# pca10040_sheet7_power_supply.net
KiCad netlist of a schematic drawn in Altium Designer
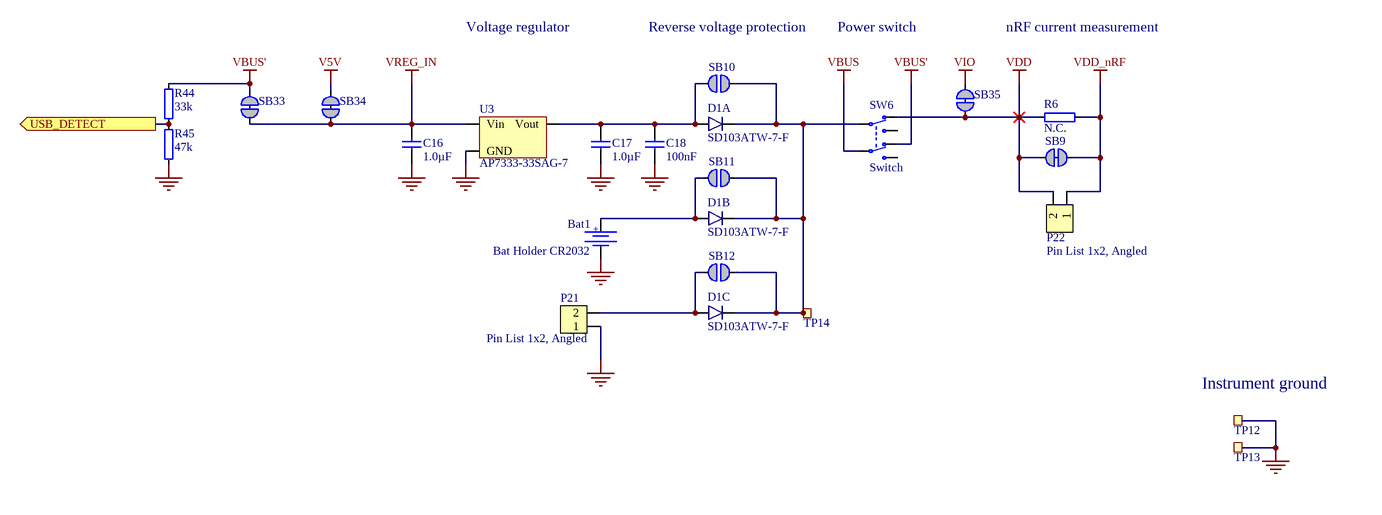
[diagram p0: pca10040_sheet7_power_supply.SchDoc]

(export (version "E")
  (design (tool "Eeschema 10.0.6"))
  (components
    (comp (ref "Bat1")
      (value "Bat Holder CR2032")
      (footprint "CR2032_HOLDER_SMD")
      (description "Bat Holder CR2032 SMD")
      (fields
        (field (name "MANUFACTURER") "Comfortable")
        (field (name "MANUFACTURER PART NUMBER") "BC-2001")
        (field (name "PUBLISHER") "Nordic Semiconductor")
      )
      (libsource (lib "Nordic Passive DB") (part "Battery"))
    )
    (comp (ref "C16")
      (value "1.0µF")
      (footprint "CAPC1608X06L")
      (description "Capacitor, X7R, ±10%")
      (fields (field (name "PART NUMBER") "C0603-1µ0") (field (name "PUBLISHER") "Nordic Semiconductor"))
      (libsource (lib "Nordic Passive DB") (part "CAP"))
    )
    (comp (ref "C17")
      (value "1.0µF")
      (footprint "CAPC1608X06L")
      (description "Capacitor, X7R, ±10%")
      (fields (field (name "PART NUMBER") "C0603-1µ0") (field (name "PUBLISHER") "Nordic Semiconductor"))
      (libsource (lib "Nordic Passive DB") (part "CAP"))
    )
    (comp (ref "C18")
      (value "100nF")
      (footprint "CAPC1005X04L")
      (description "Capacitor, X7R, ±10%")
      (fields (field (name "PART NUMBER") "C0402-100n") (field (name "PUBLISHER") "Nordic Semiconductor"))
      (libsource (lib "Nordic Passive DB") (part "CAP"))
    )
    (comp (ref "D1")
      (value "SD103ATW-7-F")
      (footprint "SOT-363")
      (description "Surface Mount Schottky Barrier Diode Array")
      (fields
        (field (name "MANUFACTURER") "Diodes Incorporated")
        (field (name "2ND SOURCE PART NUMBER") "177-3507")
        (field (name "PUBLISHER") "Nordic Semiconductor")
      )
      (libsource (lib "Nordic Discrete DB") (part "D{colon}DIODE_3_IND"))
    )
    (comp (ref "P21")
      (value "Pin List 1x2, Angled")
      (footprint "LIST_ANG_1x2-SMD-2.54MM")
      (description "Pin List 1x2, 2.54mm (100mil), Right Angled, SMD")
      (fields
        (field (name "PART NUMBER") "Pin List Ang 1x2 SMD, 2.54mm")
        (field (name "MANUFACTURER") "W-CON")
        (field (name "PUBLISHER") "Nordic Semiconductor")
      )
      (libsource (lib "") (part "CONN-2_1"))
    )
    (comp (ref "P22")
      (value "Pin List 1x2, Angled")
      (footprint "LIST_ANG_1x2-SMD-2.54MM")
      (description "Pin List 1x2, 2.54mm (100mil), Right Angled, SMD")
      (fields
        (field (name "PART NUMBER") "Pin List Ang 1x2 SMD, 2.54mm")
        (field (name "MANUFACTURER") "W-CON")
        (field (name "PUBLISHER") "Nordic Semiconductor")
      )
      (libsource (lib "Nordic Passive DB") (part "CONN-2"))
    )
    (comp (ref "R6")
      (value "N.C.")
      (footprint "RESC1005X04L")
      (description "Not mounted")
      (fields (field (name "PART NUMBER") "R0402-N.C.") (field (name "PUBLISHER") "Nordic Semiconductor"))
      (libsource (lib "Nordic Passive DB") (part "RES_1"))
    )
    (comp (ref "R44")
      (value "33k")
      (footprint "RESC1005X04L")
      (description "Resistor, ±1%, 0.063W")
      (fields (field (name "PART NUMBER") "R0402-33k") (field (name "PUBLISHER") "Nordic Semiconductor"))
      (libsource (lib "Nordic Passive DB") (part "RES_1"))
    )
    (comp (ref "R45")
      (value "47k")
      (footprint "RESC1005X04L")
      (description "Resistor, ±1%, 0.063W")
      (fields (field (name "PART NUMBER") "R0402-47k") (field (name "PUBLISHER") "Nordic Semiconductor"))
      (libsource (lib "Nordic Passive DB") (part "RES_1"))
    )
    (comp (ref "SB9")
      (value "Solderbridge")
      (footprint "Solderbridge_Shorted")
      (description "Shorted Solderbridge")
      (fields
        (field (name "PART NUMBER") "Solderbridge Shorted")
        (field (name "PUBLISHER") "Nordic Semiconductor")
      )
      (libsource (lib "Nordic Passive DB") (part "SOLDERBRIDGE_SHORTED"))
    )
    (comp (ref "SB10")
      (value "Solderbridge")
      (footprint "Solderbridge")
      (fields (field (name "PUBLISHER") "Nordic Semiconductor"))
      (libsource (lib "Nordic Passive DB") (part "SOLDERBRIDGE"))
    )
    (comp (ref "SB11")
      (value "Solderbridge")
      (footprint "Solderbridge")
      (fields (field (name "PUBLISHER") "Nordic Semiconductor"))
      (libsource (lib "Nordic Passive DB") (part "SOLDERBRIDGE"))
    )
    (comp (ref "SB12")
      (value "Solderbridge")
      (footprint "Solderbridge")
      (fields (field (name "PUBLISHER") "Nordic Semiconductor"))
      (libsource (lib "Nordic Passive DB") (part "SOLDERBRIDGE"))
    )
    (comp (ref "SB33")
      (value "Solderbridge")
      (footprint "Solderbridge_Shorted_Power")
      (description "Shorted Solderbridge Power")
      (fields
        (field (name "PART NUMBER") "Solderbridge Shorted Power")
        (field (name "PUBLISHER") "Nordic Semiconductor")
      )
      (libsource (lib "Nordic Passive DB") (part "SOLDERBRIDGE_SHORTED"))
    )
    (comp (ref "SB34")
      (value "Solderbridge")
      (footprint "Solderbridge_Shorted_Power")
      (description "Shorted Solderbridge Power")
      (fields
        (field (name "PART NUMBER") "Solderbridge Shorted Power")
        (field (name "PUBLISHER") "Nordic Semiconductor")
      )
      (libsource (lib "Nordic Passive DB") (part "SOLDERBRIDGE_SHORTED"))
    )
    (comp (ref "SB35")
      (value "Solderbridge")
      (footprint "Solderbridge_Shorted_Power")
      (description "Shorted Solderbridge Power")
      (fields
        (field (name "PART NUMBER") "Solderbridge Shorted Power")
        (field (name "PUBLISHER") "Nordic Semiconductor")
      )
      (libsource (lib "Nordic Passive DB") (part "SOLDERBRIDGE_SHORTED"))
    )
    (comp (ref "SW6")
      (value "Switch")
      (footprint "Switch-Slide-DPDT-8.5x3.6mm")
      (description "SMD slide Switch (ON-ON)")
      (fields
        (field (name "PART NUMBER") "Switch-Slide-DPDT-8.5x3.6mm")
        (field (name "MANUFACTURER") "Dailywell")
        (field (name "PUBLISHER") "Nordic Semiconductor")
      )
      (libsource (lib "Nordic Discrete DB") (part "SW-DPDT"))
    )
    (comp (ref "TP12")
      (value "TP")
      (footprint "TESTPAD-TH")
      (description "Testpoint, through hole")
      (fields (field (name "PART NUMBER") "Testpoint TH") (field (name "PUBLISHER") "Nordic Semiconductor"))
      (libsource (lib "Nordic Passive DB") (part "TESTPAD"))
    )
    (comp (ref "TP13")
      (value "TP")
      (footprint "TESTPAD-TH")
      (description "Testpoint, through hole")
      (fields (field (name "PART NUMBER") "Testpoint TH") (field (name "PUBLISHER") "Nordic Semiconductor"))
      (libsource (lib "Nordic Passive DB") (part "TESTPAD"))
    )
    (comp (ref "TP14")
      (value "Ø1.0mm,SMD")
      (footprint "TP_SMD_Ø1.0mm")
      (description "1.0mm circular SMD testpad")
      (fields
        (field (name "PART NUMBER") "TP_SMD_Ø1.0MM")
        (field (name "MANUFACTURER") "Nordic Semiconductor")
        (field (name "PUBLISHER") "Nordic Semiconductor")
      )
      (libsource (lib "") (part "TESTPAD_1"))
    )
    (comp (ref "U3")
      (value "AP7333-33SAG-7")
      (footprint "SOT-23A")
      (description "300mA, Low Quiescent Current, Fast Transient Low Dropout Linear Regulator")
      (fields
        (field (name "MANUFACTURER") "Diodes Incorporated")
        (field (name "PUBLISHER") "Nordic Semiconductor")
      )
      (libsource (lib "Nordic Active DB") (part "AP7333-XXSAG"))
    )
  )
  (nets
    (net (code "1") (name "/USB_DETECT") (class "Default")
      (node (ref "R44") (pin "1") (pinfunction "1_1") (pintype "passive"))
      (node (ref "R45") (pin "2") (pinfunction "2_2") (pintype "passive"))
    )
    (net (code "2") (name "GND") (class "Default")
      (node (ref "Bat1") (pin "2") (pintype "passive"))
      (node (ref "C16") (pin "1") (pinfunction "1_1") (pintype "passive"))
      (node (ref "C17") (pin "1") (pinfunction "1_1") (pintype "passive"))
      (node (ref "C18") (pin "1") (pinfunction "1_1") (pintype "passive"))
      (node (ref "P21") (pin "1") (pinfunction "1_1") (pintype "passive"))
      (node (ref "R45") (pin "1") (pinfunction "1_1") (pintype "passive"))
      (node (ref "TP12") (pin "1") (pinfunction "1_1") (pintype "passive"))
      (node (ref "TP13") (pin "1") (pinfunction "1_1") (pintype "passive"))
      (node (ref "U3") (pin "3") (pinfunction "GND_3") (pintype "passive"))
    )
    (net (code "3") (name "Net-(D1A-A1)") (class "Default")
      (node (ref "C17") (pin "2") (pinfunction "2_2") (pintype "passive"))
      (node (ref "C18") (pin "2") (pinfunction "2_2") (pintype "passive"))
      (node (ref "D1") (pin "6") (pinfunction "A1_6") (pintype "passive"))
      (node (ref "SB10") (pin "2") (pinfunction "1_2") (pintype "passive"))
      (node (ref "U3") (pin "2") (pinfunction "Vout_2") (pintype "passive"))
    )
    (net (code "4") (name "Net-(D1A-C1)") (class "Default")
      (node (ref "D1") (pin "1") (pinfunction "C1_1") (pintype "passive"))
      (node (ref "D1") (pin "2") (pinfunction "C2_2") (pintype "passive"))
      (node (ref "D1") (pin "3") (pinfunction "C3_3") (pintype "passive"))
      (node (ref "SB10") (pin "1") (pinfunction "0_1") (pintype "passive"))
      (node (ref "SB11") (pin "1") (pinfunction "0_1") (pintype "passive"))
      (node (ref "SB12") (pin "1") (pinfunction "0_1") (pintype "passive"))
      (node (ref "SW6") (pin "2") (pinfunction "COM-1_2") (pintype "passive"))
      (node (ref "TP14") (pin "1") (pinfunction "1_1") (pintype "passive"))
    )
    (net (code "5") (name "Net-(D1B-A2)") (class "Default")
      (node (ref "Bat1") (pin "1") (pintype "passive"))
      (node (ref "D1") (pin "5") (pinfunction "A2_5") (pintype "passive"))
      (node (ref "SB11") (pin "2") (pinfunction "1_2") (pintype "passive"))
    )
    (net (code "6") (name "Net-(D1C-A3)") (class "Default")
      (node (ref "D1") (pin "4") (pinfunction "A3_4") (pintype "passive"))
      (node (ref "P21") (pin "2") (pinfunction "2_2") (pintype "passive"))
      (node (ref "SB12") (pin "2") (pinfunction "1_2") (pintype "passive"))
    )
    (net (code "7") (name "V5V") (class "Default")
      (node (ref "SB34") (pin "1") (pinfunction "0_1") (pintype "passive"))
    )
    (net (code "8") (name "VBUS") (class "Default")
      (node (ref "SW6") (pin "5") (pinfunction "COM-2_5") (pintype "passive"))
    )
    (net (code "9") (name "VBUS'") (class "Default")
      (node (ref "R44") (pin "2") (pinfunction "2_2") (pintype "passive"))
      (node (ref "SB33") (pin "1") (pinfunction "0_1") (pintype "passive"))
      (node (ref "SW6") (pin "6") (pinfunction "N.C-2_6") (pintype "passive"))
    )
    (net (code "10") (name "VDD") (class "Default")
      (node (ref "P22") (pin "2") (pinfunction "2_2") (pintype "passive"))
      (node (ref "R6") (pin "1") (pinfunction "1_1") (pintype "passive"))
      (node (ref "SB35") (pin "2") (pinfunction "1_2") (pintype "passive"))
      (node (ref "SB9") (pin "2") (pinfunction "1_2") (pintype "passive"))
      (node (ref "SW6") (pin "3") (pinfunction "N.C-1_3") (pintype "passive"))
    )
    (net (code "11") (name "VDD_nRF") (class "Default")
      (node (ref "P22") (pin "1") (pinfunction "1_1") (pintype "passive"))
      (node (ref "R6") (pin "2") (pinfunction "2_2") (pintype "passive"))
      (node (ref "SB9") (pin "1") (pinfunction "0_1") (pintype "passive"))
    )
    (net (code "12") (name "VIO") (class "Default")
      (node (ref "SB35") (pin "1") (pinfunction "0_1") (pintype "passive"))
    )
    (net (code "13") (name "VREG_IN") (class "Default")
      (node (ref "C16") (pin "2") (pinfunction "2_2") (pintype "passive"))
      (node (ref "SB33") (pin "2") (pinfunction "1_2") (pintype "passive"))
      (node (ref "SB34") (pin "2") (pinfunction "1_2") (pintype "passive"))
      (node (ref "U3") (pin "1") (pinfunction "Vin_1") (pintype "passive"))
    )
    (net (code "14") (name "unconnected-(SW6-N.O-1-Pad1)") (class "Default")
      (node (ref "SW6") (pin "1") (pinfunction "N.O-1_1") (pintype "passive"))
    )
    (net (code "15") (name "unconnected-(SW6-N.O-2-Pad4)") (class "Default")
      (node (ref "SW6") (pin "4") (pinfunction "N.O-2_4") (pintype "passive"))
    )
  )
)
